# PowerAmplifier_BFU590G.net
KiCad netlist of a schematic drawn in Altium Designer
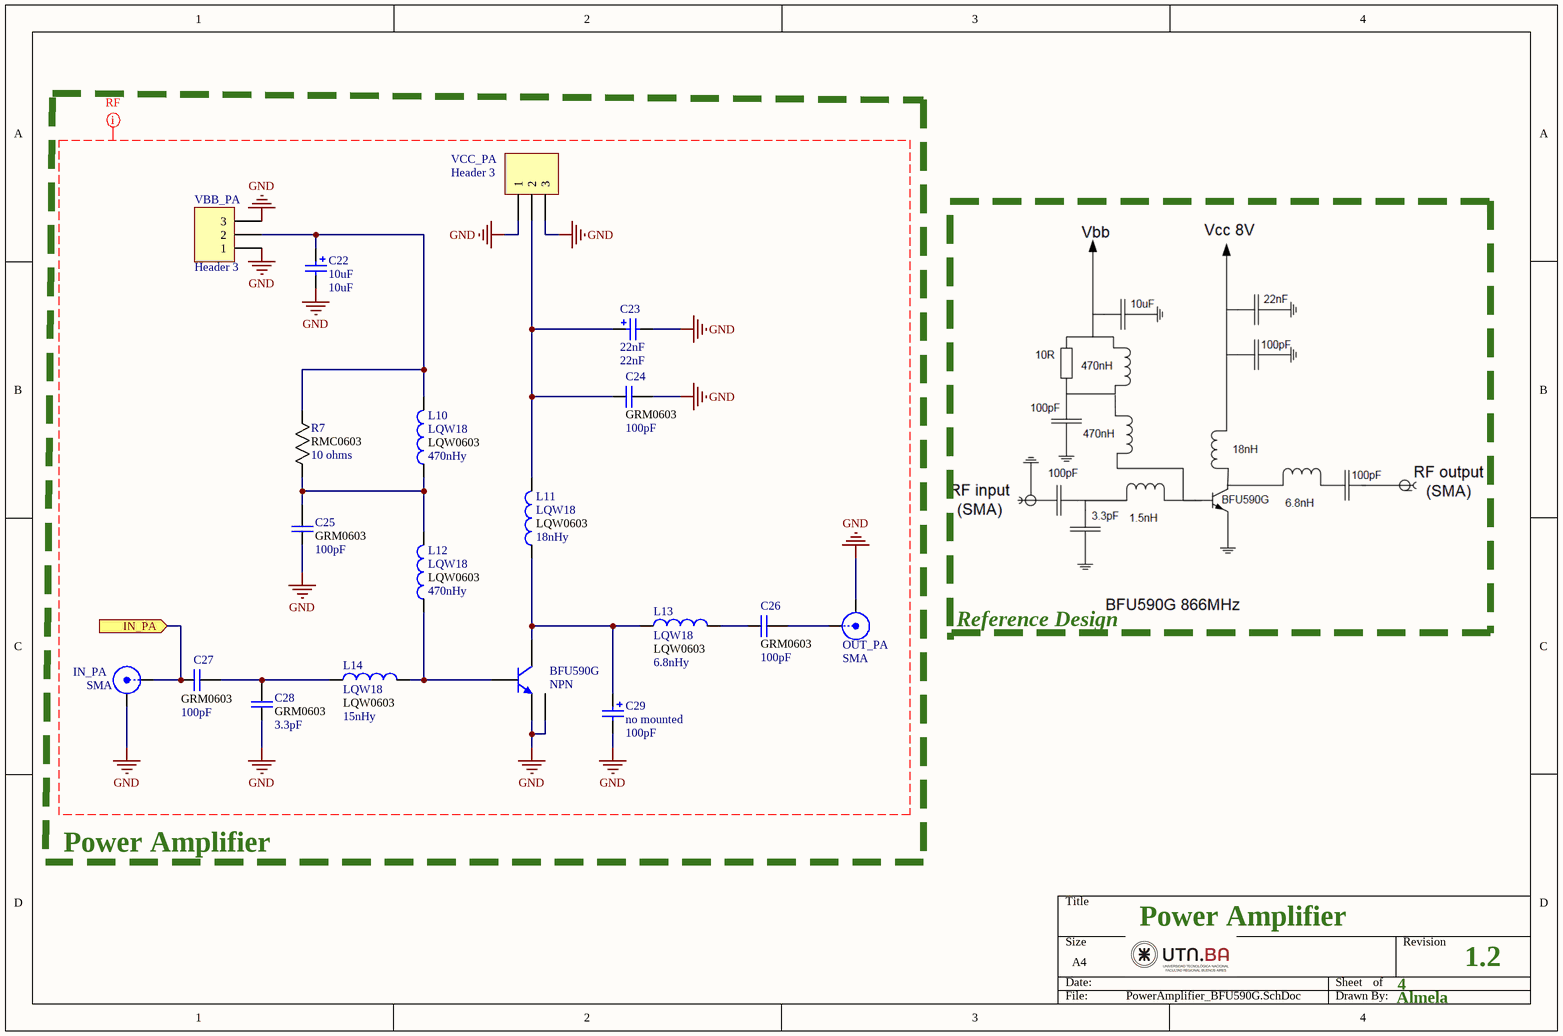
[diagram p0: PowerAmplifier_BFU590G.SchDoc]

(export (version "E")
  (design (tool "Eeschema 10.0.6"))
  (components
    (comp (ref "BFU590G")
      (value "NPN")
      (footprint "SOT223_L")
      (description "NPN Bipolar Transistor")
      (fields (field (name "PUBLISHER") "Altium Limited"))
      (libsource (lib "Radar_RF_EAIII") (part "BFU590G"))
    )
    (comp (ref "C22")
      (value "10uF")
      (footprint "6-0805_N")
      (description "Polarized Capacitor (Axial)")
      (fields (field (name "ALTIUM_VALUE") "10uF") (field (name "PUBLISHER") "Altium Limited"))
      (libsource (lib "Radar_RF_EAIII") (part "Cap Pol2_7"))
    )
    (comp (ref "C23")
      (value "22nF")
      (footprint "6-0805_N")
      (description "Polarized Capacitor (Axial)")
      (fields (field (name "ALTIUM_VALUE") "22nF") (field (name "PUBLISHER") "Altium Limited"))
      (libsource (lib "PCB_Project") (part "Cap Pol2_1"))
    )
    (comp (ref "C24")
      (value "100pF")
      (footprint "GRM0603")
      (description "Capacitor GRM18 0603")
      (fields (field (name "Comment") "Cap 0603") (field (name "PUBLISHER") "Altium Limited"))
      (libsource (lib "Radar_RF_EAIII") (part "Cap"))
    )
    (comp (ref "C25")
      (value "100pF")
      (footprint "GRM0603")
      (description "Capacitor GRM18 0603")
      (fields (field (name "Comment") "Cap 0603") (field (name "PUBLISHER") "Altium Limited"))
      (libsource (lib "Radar_RF_EAIII") (part "Cap"))
    )
    (comp (ref "C26")
      (value "100pF")
      (footprint "GRM0603")
      (description "Capacitor GRM18 0603")
      (fields (field (name "Comment") "Cap 0603") (field (name "PUBLISHER") "Altium Limited"))
      (libsource (lib "Radar_RF_EAIII") (part "Cap"))
    )
    (comp (ref "C27")
      (value "100pF")
      (footprint "GRM0603")
      (description "Capacitor GRM18 0603")
      (fields (field (name "Comment") "Cap 0603") (field (name "PUBLISHER") "Altium Limited"))
      (libsource (lib "Radar_RF_EAIII") (part "Cap"))
    )
    (comp (ref "C28")
      (value "3.3pF")
      (footprint "GRM0603")
      (description "Capacitor GRM18 0603")
      (fields (field (name "Comment") "Cap 0603") (field (name "PUBLISHER") "Altium Limited"))
      (libsource (lib "Radar_RF_EAIII") (part "Cap"))
    )
    (comp (ref "C29")
      (value "no mounted")
      (footprint "6-0805_N")
      (description "Polarized Capacitor (Axial)")
      (fields (field (name "ALTIUM_VALUE") "100pF") (field (name "PUBLISHER") "Altium Limited"))
      (libsource (lib "PCB_Project") (part "Cap Pol2_1"))
    )
    (comp (ref "IN_PA")
      (value "SMA")
      (footprint "SMA-142-0701-851")
      (description "SMA Straight Connector")
      (fields (field (name "PUBLISHER") "Altium Limited"))
      (libsource (lib "Radar_RF_EAIII") (part "SMA"))
    )
    (comp (ref "L10")
      (value "LQW18")
      (footprint "INDC1608X100N")
      (description "Ind RF Chip Wirewound 18nH 5% 100MHz 40Q-Factor 550mA 0603 Paper T/R")
      (fields
        (field (name "MP") "LQW18AN18NJ00D")
        (field (name "PARAMETER 1") "LQW0603")
        (field (name "ALTIUM_VALUE") "470nHy")
      )
      (libsource (lib "Radar_RF_EAIII") (part "LQW18"))
    )
    (comp (ref "L11")
      (value "LQW18")
      (footprint "INDC1608X100N")
      (description "Ind RF Chip Wirewound 18nH 5% 100MHz 40Q-Factor 550mA 0603 Paper T/R")
      (fields
        (field (name "MP") "LQW18AN18NJ00D")
        (field (name "PARAMETER 1") "LQW0603")
        (field (name "ALTIUM_VALUE") "18nHy")
      )
      (libsource (lib "Radar_RF_EAIII") (part "LQW18"))
    )
    (comp (ref "L12")
      (value "LQW18")
      (footprint "INDC1608X100N")
      (description "Ind RF Chip Wirewound 18nH 5% 100MHz 40Q-Factor 550mA 0603 Paper T/R")
      (fields
        (field (name "MP") "LQW18AN18NJ00D")
        (field (name "PARAMETER 1") "LQW0603")
        (field (name "ALTIUM_VALUE") "470nHy")
      )
      (libsource (lib "Radar_RF_EAIII") (part "LQW18"))
    )
    (comp (ref "L13")
      (value "LQW18")
      (footprint "INDC1608X100N")
      (description "Ind RF Chip Wirewound 18nH 5% 100MHz 40Q-Factor 550mA 0603 Paper T/R")
      (fields
        (field (name "MP") "LQW18AN18NJ00D")
        (field (name "PARAMETER 1") "LQW0603")
        (field (name "ALTIUM_VALUE") "6.8nHy")
      )
      (libsource (lib "Radar_RF_EAIII") (part "LQW18"))
    )
    (comp (ref "L14")
      (value "LQW18")
      (footprint "INDC1608X100N")
      (description "Ind RF Chip Wirewound 18nH 5% 100MHz 40Q-Factor 550mA 0603 Paper T/R")
      (fields
        (field (name "MP") "LQW18AN18NJ00D")
        (field (name "PARAMETER 1") "LQW0603")
        (field (name "ALTIUM_VALUE") "15nHy")
      )
      (libsource (lib "Radar_RF_EAIII") (part "LQW18"))
    )
    (comp (ref "OUT_PA")
      (value "SMA")
      (footprint "SMA-142-0701-851")
      (description "SMA Straight Connector")
      (fields (field (name "PUBLISHER") "Altium Limited"))
      (libsource (lib "Radar_RF_EAIII") (part "SMA"))
    )
    (comp (ref "R7")
      (value "10 ohms")
      (footprint "RMC0603")
      (description "Resistor RMC0603")
      (fields (field (name "Comment") "Resistor"))
      (libsource (lib "Radar_RF_EAIII") (part "Resistor"))
    )
    (comp (ref "VBB_PA")
      (value "Header 3")
      (footprint "HDR1X3")
      (description "Header, 3-Pin")
      (fields (field (name "PUBLISHER") "Altium Limited"))
      (libsource (lib "Miscellaneous Connectors") (part "Header 3"))
    )
    (comp (ref "VCC_PA")
      (value "Header 3")
      (footprint "HDR1X3")
      (description "Header, 3-Pin")
      (fields (field (name "PUBLISHER") "Altium Limited"))
      (libsource (lib "") (part "Header 3_1"))
    )
  )
  (nets
    (net (code "1") (name "/IN_PA") (class "Default")
      (node (ref "C27") (pin "1") (pinfunction "1_1") (pintype "passive"))
      (node (ref "IN_PA") (pin "1") (pinfunction "X_1") (pintype "passive"))
    )
    (net (code "2") (name "GND") (class "Default")
      (node (ref "BFU590G") (pin "1") (pinfunction "E_1") (pintype "passive"))
      (node (ref "BFU590G") (pin "3") (pinfunction "E_3") (pintype "passive"))
      (node (ref "C22") (pin "2") (pinfunction "2_2") (pintype "passive"))
      (node (ref "C23") (pin "2") (pinfunction "2_2") (pintype "passive"))
      (node (ref "C24") (pin "2") (pinfunction "2_2") (pintype "passive"))
      (node (ref "C25") (pin "1") (pinfunction "1_1") (pintype "passive"))
      (node (ref "C28") (pin "1") (pinfunction "1_1") (pintype "passive"))
      (node (ref "C29") (pin "2") (pinfunction "2_2") (pintype "passive"))
      (node (ref "IN_PA") (pin "2") (pinfunction "Y_2") (pintype "passive"))
      (node (ref "OUT_PA") (pin "2") (pinfunction "Y_2") (pintype "passive"))
      (node (ref "VBB_PA") (pin "1") (pinfunction "1_1") (pintype "passive"))
      (node (ref "VBB_PA") (pin "3") (pinfunction "3_3") (pintype "passive"))
      (node (ref "VCC_PA") (pin "1") (pinfunction "1_1") (pintype "passive"))
      (node (ref "VCC_PA") (pin "3") (pinfunction "3_3") (pintype "passive"))
    )
    (net (code "3") (name "Net-(BFU590G-B)") (class "Default")
      (node (ref "BFU590G") (pin "2") (pinfunction "B_2") (pintype "passive"))
      (node (ref "L12") (pin "1") (pinfunction "1_1") (pintype "passive"))
      (node (ref "L14") (pin "2") (pinfunction "2_2") (pintype "passive"))
    )
    (net (code "4") (name "Net-(BFU590G-C)") (class "Default")
      (node (ref "BFU590G") (pin "4") (pinfunction "C_4") (pintype "passive"))
      (node (ref "C29") (pin "1") (pinfunction "1_1") (pintype "passive"))
      (node (ref "L11") (pin "1") (pinfunction "1_1") (pintype "passive"))
      (node (ref "L13") (pin "1") (pinfunction "1_1") (pintype "passive"))
    )
    (net (code "5") (name "Net-(C22-Pad1)") (class "Default")
      (node (ref "C22") (pin "1") (pinfunction "1_1") (pintype "passive"))
      (node (ref "L10") (pin "2") (pinfunction "2_2") (pintype "passive"))
      (node (ref "R7") (pin "2") (pinfunction "2_2") (pintype "passive"))
      (node (ref "VBB_PA") (pin "2") (pinfunction "2_2") (pintype "passive"))
    )
    (net (code "6") (name "Net-(C23-Pad1)") (class "Default")
      (node (ref "C23") (pin "1") (pinfunction "1_1") (pintype "passive"))
      (node (ref "C24") (pin "1") (pinfunction "1_1") (pintype "passive"))
      (node (ref "L11") (pin "2") (pinfunction "2_2") (pintype "passive"))
      (node (ref "VCC_PA") (pin "2") (pinfunction "2_2") (pintype "passive"))
    )
    (net (code "7") (name "Net-(C25-Pad2)") (class "Default")
      (node (ref "C25") (pin "2") (pinfunction "2_2") (pintype "passive"))
      (node (ref "L10") (pin "1") (pinfunction "1_1") (pintype "passive"))
      (node (ref "L12") (pin "2") (pinfunction "2_2") (pintype "passive"))
      (node (ref "R7") (pin "1") (pinfunction "1_1") (pintype "passive"))
    )
    (net (code "8") (name "Net-(C26-Pad1)") (class "Default")
      (node (ref "C26") (pin "1") (pinfunction "1_1") (pintype "passive"))
      (node (ref "L13") (pin "2") (pinfunction "2_2") (pintype "passive"))
    )
    (net (code "9") (name "Net-(C27-Pad2)") (class "Default")
      (node (ref "C27") (pin "2") (pinfunction "2_2") (pintype "passive"))
      (node (ref "C28") (pin "2") (pinfunction "2_2") (pintype "passive"))
      (node (ref "L14") (pin "1") (pinfunction "1_1") (pintype "passive"))
    )
    (net (code "10") (name "Net-(OUT_PA-X)") (class "Default")
      (node (ref "C26") (pin "2") (pinfunction "2_2") (pintype "passive"))
      (node (ref "OUT_PA") (pin "1") (pinfunction "X_1") (pintype "passive"))
    )
  )
)
